# midi_block_template.net
KiCad netlist of a schematic drawn in EAGLE
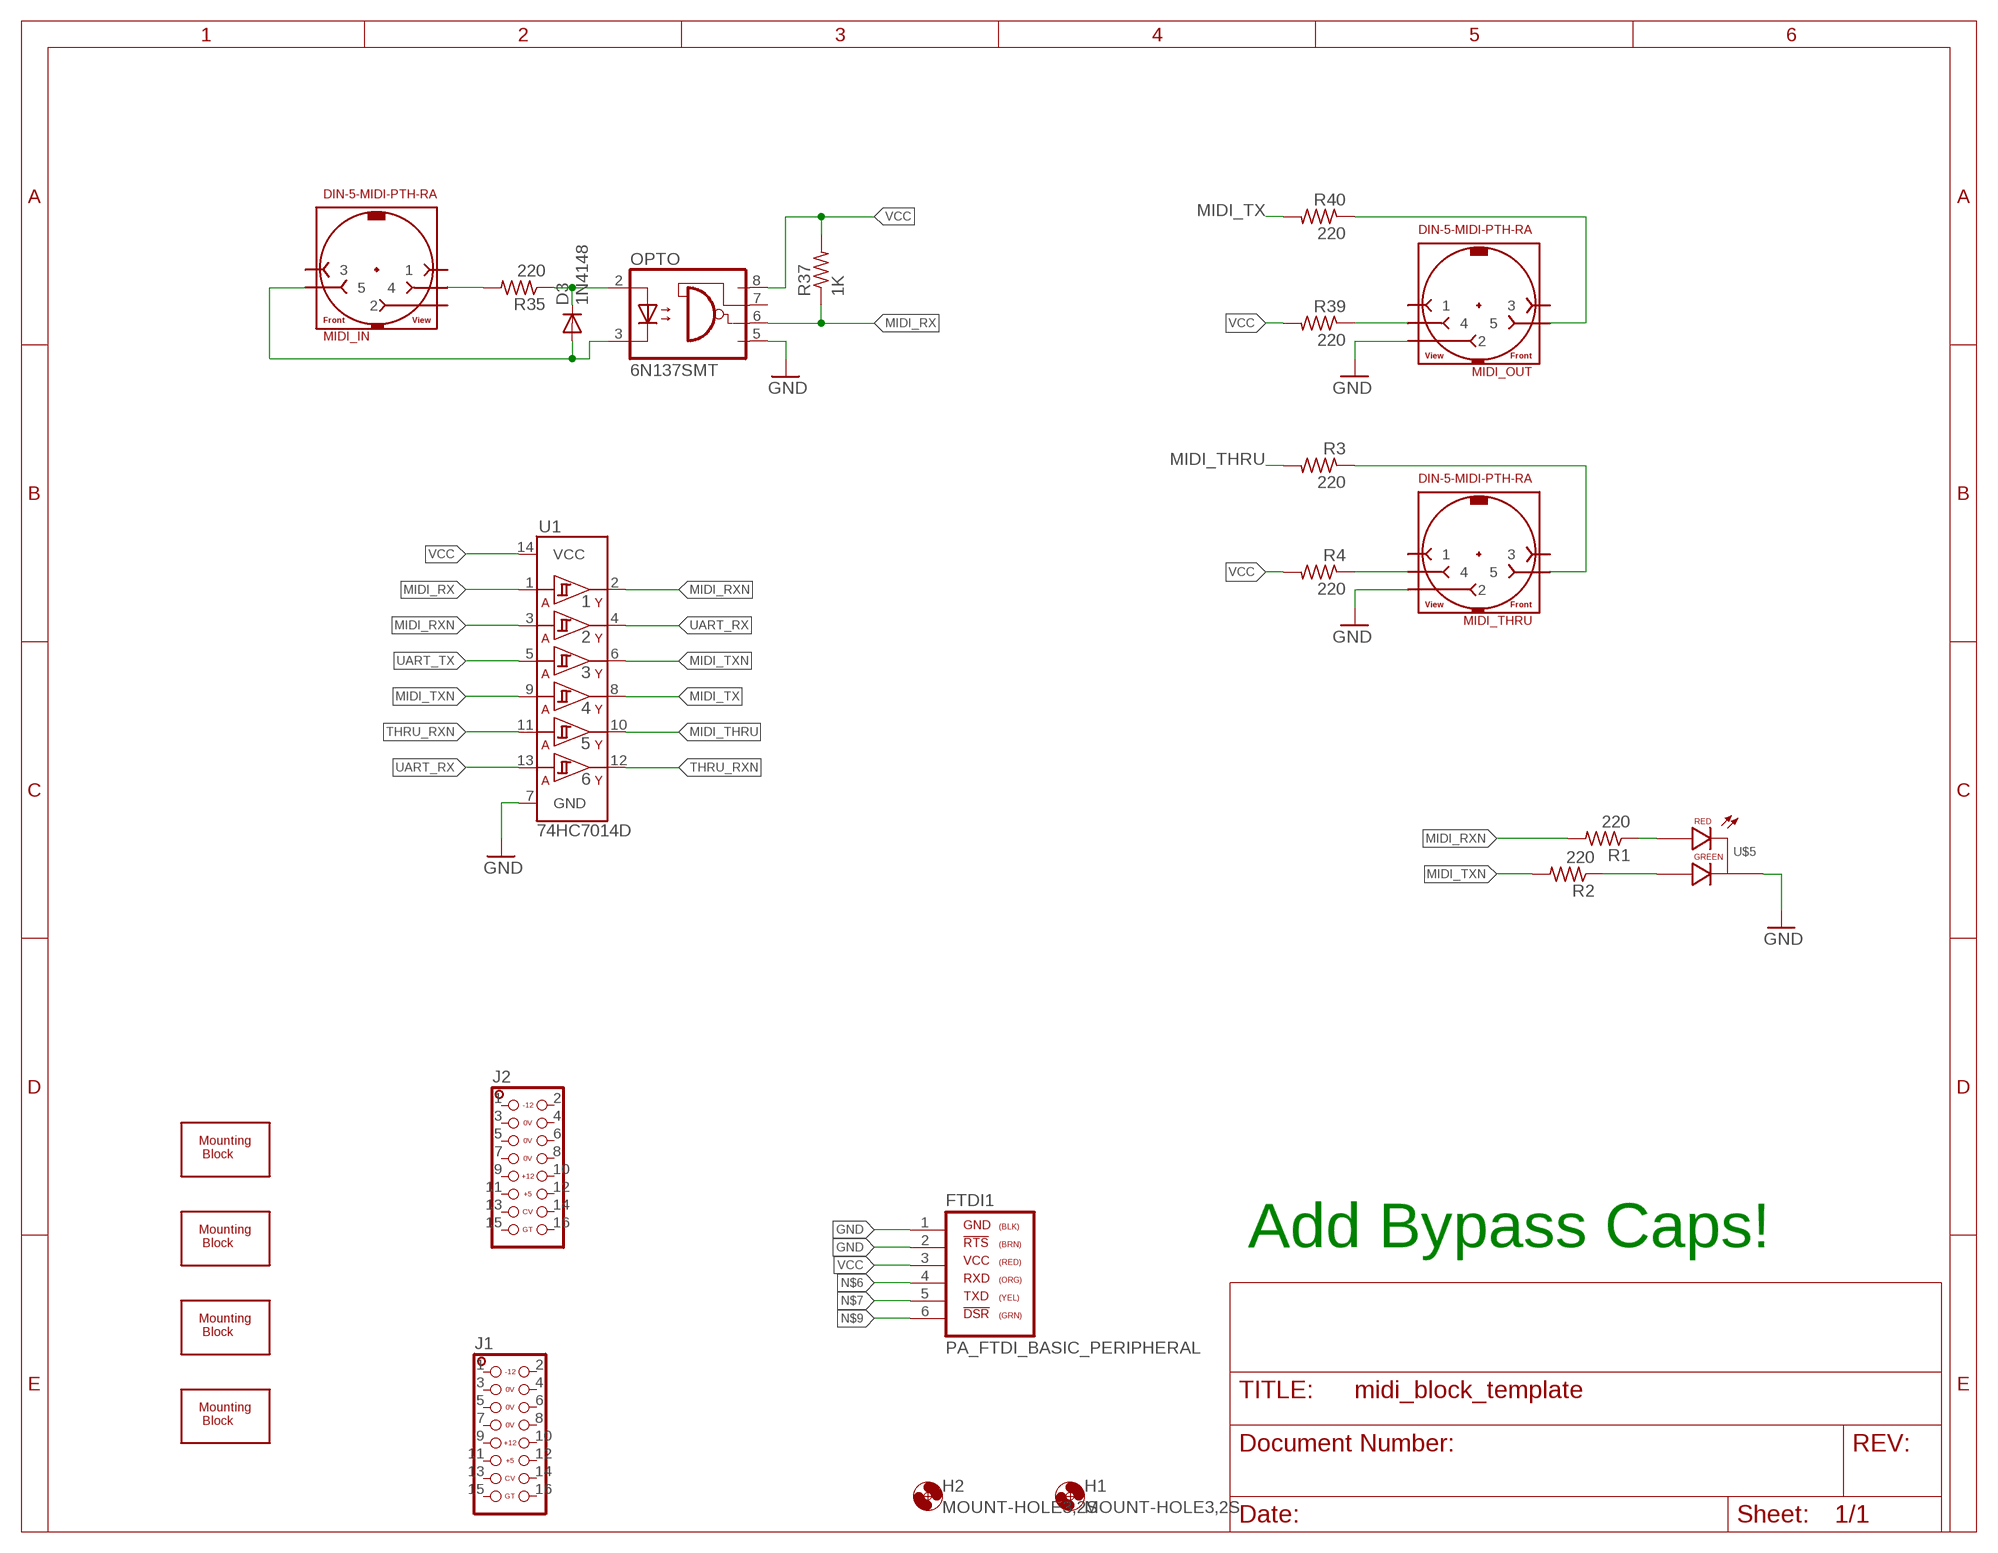
[diagram p0: schematic, sheet 1]

(export (version "E")
  (design (tool "Eeschema 10.0.6"))
  (components
    (comp (ref "D3")
      (value "1N4148")
      (footprint "eagle-import:SOD323-W")
      (libsource (lib "eagle-import") (part "DIODE-SOD323-W"))
    )
    (comp (ref "FTDI1")
      (value "PA_FTDI_BASIC_PERIPHERAL")
      (footprint "eagle-import:PA_PMOD_SIL_MALE")
      (libsource (lib "eagle-import") (part "PA_FTDI_BASIC_PERIPHERAL"))
    )
    (comp (ref "H1")
      (value "MOUNT-HOLE3,2S")
      (footprint "eagle-import:3,2,SMALL")
      (libsource (lib "eagle-import") (part "MOUNT-HOLE3,2S"))
    )
    (comp (ref "H2")
      (value "MOUNT-HOLE3,2S")
      (footprint "eagle-import:3,2,SMALL")
      (libsource (lib "eagle-import") (part "MOUNT-HOLE3,2S"))
    )
    (comp (ref "J1")
      (value "EUROPWR_2X08-SHROUD")
      (footprint "eagle-import:2X08_EUROPWR_SHROUD")
      (libsource (lib "eagle-import") (part "EUROPWR_2X08-SHROUD"))
    )
    (comp (ref "J2")
      (value "EUROPWR_2X08-SHROUD")
      (footprint "eagle-import:2X08_EUROPWR_SHROUD")
      (libsource (lib "eagle-import") (part "EUROPWR_2X08-SHROUD"))
    )
    (comp (ref "MIDI_IN")
      (value "DIN-5-MIDI-PTH-RA")
      (footprint "eagle-import:DIN-5-PTH-RA-SUPPORT")
      (libsource (lib "eagle-import") (part "DIN-5-MIDI-PTH-RA"))
    )
    (comp (ref "MIDI_OUT")
      (value "DIN-5-MIDI-PTH-RA")
      (footprint "eagle-import:DIN-5-PTH-RA-SUPPORT")
      (libsource (lib "eagle-import") (part "DIN-5-MIDI-PTH-RA"))
    )
    (comp (ref "MIDI_THRU")
      (value "DIN-5-MIDI-PTH-RA")
      (footprint "eagle-import:DIN-5-PTH-RA-SUPPORT")
      (libsource (lib "eagle-import") (part "DIN-5-MIDI-PTH-RA"))
    )
    (comp (ref "OPTO")
      (value "6N137SMT")
      (footprint "eagle-import:DIL8-SMD")
      (libsource (lib "eagle-import") (part "6N137SMT"))
    )
    (comp (ref "R1")
      (value "220")
      (footprint "eagle-import:R0603")
      (libsource (lib "eagle-import") (part "R-US_R0603"))
    )
    (comp (ref "R2")
      (value "220")
      (footprint "eagle-import:R0603")
      (libsource (lib "eagle-import") (part "R-US_R0603"))
    )
    (comp (ref "R3")
      (value "220")
      (footprint "eagle-import:R0603")
      (libsource (lib "eagle-import") (part "R-US_R0603"))
    )
    (comp (ref "R4")
      (value "220")
      (footprint "eagle-import:R0603")
      (libsource (lib "eagle-import") (part "R-US_R0603"))
    )
    (comp (ref "R35")
      (value "220")
      (footprint "eagle-import:R0603")
      (libsource (lib "eagle-import") (part "R-US_R0603"))
    )
    (comp (ref "R37")
      (value "1K")
      (footprint "eagle-import:R0603")
      (libsource (lib "eagle-import") (part "R-US_R0603"))
    )
    (comp (ref "R39")
      (value "220")
      (footprint "eagle-import:R0603")
      (libsource (lib "eagle-import") (part "R-US_R0603"))
    )
    (comp (ref "R40")
      (value "220")
      (footprint "eagle-import:R0603")
      (libsource (lib "eagle-import") (part "R-US_R0603"))
    )
    (comp (ref "U$1")
      (value "PCB-MB-SIDE")
      (footprint "eagle-import:PCB-MB-01-SIDE")
      (libsource (lib "eagle-import") (part "PCB-MB-SIDE"))
    )
    (comp (ref "U$2")
      (value "PCB-MB-SIDE")
      (footprint "eagle-import:PCB-MB-01-SIDE")
      (libsource (lib "eagle-import") (part "PCB-MB-SIDE"))
    )
    (comp (ref "U$3")
      (value "PCB-MB-SIDE")
      (footprint "eagle-import:PCB-MB-01-SIDE")
      (libsource (lib "eagle-import") (part "PCB-MB-SIDE"))
    )
    (comp (ref "U$4")
      (value "PCB-MB-SIDE")
      (footprint "eagle-import:PCB-MB-01-SIDE")
      (libsource (lib "eagle-import") (part "PCB-MB-SIDE"))
    )
    (comp (ref "U$5")
      (value "LED-RG-CC-PTH-G18500")
      (footprint "eagle-import:LED-RG-PANEL")
      (libsource (lib "eagle-import") (part "LED-RG-CC-PTH-G18500"))
    )
    (comp (ref "U1")
      (value "74HC7014D")
      (footprint "eagle-import:SOIC-14")
      (libsource (lib "eagle-import") (part "74HC7014D"))
    )
  )
  (nets
    (net (code "1") (name "GND") (class "Default")
      (node (ref "FTDI1") (pin "1") (pinfunction "1_1") (pintype "passive"))
      (node (ref "FTDI1") (pin "2") (pinfunction "2_2") (pintype "passive"))
      (node (ref "MIDI_OUT") (pin "2") (pinfunction "2_2") (pintype "bidirectional"))
      (node (ref "MIDI_THRU") (pin "2") (pinfunction "2_2") (pintype "bidirectional"))
      (node (ref "OPTO") (pin "5") (pinfunction "GND_5") (pintype "passive"))
      (node (ref "U$5") (pin "CC") (pinfunction "CATHODE_CC") (pintype "bidirectional"))
      (node (ref "U1") (pin "7") (pinfunction "GND_7") (pintype "power_in"))
    )
    (net (code "2") (name "MIDI_RX") (class "Default")
      (node (ref "OPTO") (pin "6") (pinfunction "VO_6") (pintype "passive"))
      (node (ref "R37") (pin "1") (pinfunction "1_1") (pintype "passive"))
      (node (ref "U1") (pin "1") (pinfunction "1A_1") (pintype "input"))
    )
    (net (code "3") (name "MIDI_RXN") (class "Default")
      (node (ref "R1") (pin "2") (pinfunction "2_2") (pintype "passive"))
      (node (ref "U1") (pin "2") (pinfunction "1Y_2") (pintype "output"))
      (node (ref "U1") (pin "3") (pinfunction "2A_3") (pintype "input"))
    )
    (net (code "4") (name "MIDI_THRU") (class "Default")
      (node (ref "R3") (pin "2") (pinfunction "2_2") (pintype "passive"))
      (node (ref "U1") (pin "10") (pinfunction "5Y_10") (pintype "output"))
    )
    (net (code "5") (name "MIDI_TX") (class "Default")
      (node (ref "R40") (pin "2") (pinfunction "2_2") (pintype "passive"))
      (node (ref "U1") (pin "8") (pinfunction "4Y_8") (pintype "output"))
    )
    (net (code "6") (name "MIDI_TXN") (class "Default")
      (node (ref "R2") (pin "2") (pinfunction "2_2") (pintype "passive"))
      (node (ref "U1") (pin "6") (pinfunction "3Y_6") (pintype "output"))
      (node (ref "U1") (pin "9") (pinfunction "4A_9") (pintype "input"))
    )
    (net (code "7") (name "N$6") (class "Default")
      (node (ref "FTDI1") (pin "4") (pinfunction "4_4") (pintype "passive"))
    )
    (net (code "8") (name "N$7") (class "Default")
      (node (ref "FTDI1") (pin "5") (pinfunction "5_5") (pintype "passive"))
    )
    (net (code "9") (name "N$9") (class "Default")
      (node (ref "FTDI1") (pin "6") (pinfunction "6_6") (pintype "passive"))
    )
    (net (code "10") (name "Net-(MIDI_IN-Pad4)") (class "Default")
      (node (ref "MIDI_IN") (pin "4") (pinfunction "4_4") (pintype "bidirectional"))
      (node (ref "R35") (pin "2") (pinfunction "2_2") (pintype "passive"))
    )
    (net (code "11") (name "Net-(MIDI_OUT-Pad4)") (class "Default")
      (node (ref "MIDI_OUT") (pin "4") (pinfunction "4_4") (pintype "bidirectional"))
      (node (ref "R39") (pin "1") (pinfunction "1_1") (pintype "passive"))
    )
    (net (code "12") (name "Net-(MIDI_OUT-Pad5)") (class "Default")
      (node (ref "MIDI_OUT") (pin "5") (pinfunction "5_5") (pintype "bidirectional"))
      (node (ref "R40") (pin "1") (pinfunction "1_1") (pintype "passive"))
    )
    (net (code "13") (name "Net-(MIDI_THRU-Pad4)") (class "Default")
      (node (ref "MIDI_THRU") (pin "4") (pinfunction "4_4") (pintype "bidirectional"))
      (node (ref "R4") (pin "1") (pinfunction "1_1") (pintype "passive"))
    )
    (net (code "14") (name "Net-(MIDI_THRU-Pad5)") (class "Default")
      (node (ref "MIDI_THRU") (pin "5") (pinfunction "5_5") (pintype "bidirectional"))
      (node (ref "R3") (pin "1") (pinfunction "1_1") (pintype "passive"))
    )
    (net (code "15") (name "Net-(OPTO-A)") (class "Default")
      (node (ref "D3") (pin "C") (pinfunction "C_C") (pintype "passive"))
      (node (ref "OPTO") (pin "2") (pinfunction "A_2") (pintype "passive"))
      (node (ref "R35") (pin "1") (pinfunction "1_1") (pintype "passive"))
    )
    (net (code "16") (name "Net-(OPTO-C)") (class "Default")
      (node (ref "D3") (pin "A") (pinfunction "A_A") (pintype "passive"))
      (node (ref "MIDI_IN") (pin "5") (pinfunction "5_5") (pintype "bidirectional"))
      (node (ref "OPTO") (pin "3") (pinfunction "C_3") (pintype "passive"))
    )
    (net (code "17") (name "Net-(U$5-GREEN_CATHODE)") (class "Default")
      (node (ref "R2") (pin "1") (pinfunction "1_1") (pintype "passive"))
      (node (ref "U$5") (pin "GREEN") (pinfunction "GREEN_CATHODE_GREEN") (pintype "bidirectional"))
    )
    (net (code "18") (name "Net-(U$5-RED_CATHODE)") (class "Default")
      (node (ref "R1") (pin "1") (pinfunction "1_1") (pintype "passive"))
      (node (ref "U$5") (pin "RED") (pinfunction "RED_CATHODE_RED") (pintype "bidirectional"))
    )
    (net (code "19") (name "THRU_RXN") (class "Default")
      (node (ref "U1") (pin "11") (pinfunction "5A_11") (pintype "input"))
      (node (ref "U1") (pin "12") (pinfunction "6Y_12") (pintype "output"))
    )
    (net (code "20") (name "UART_RX") (class "Default")
      (node (ref "U1") (pin "13") (pinfunction "6A_13") (pintype "input"))
      (node (ref "U1") (pin "4") (pinfunction "2Y_4") (pintype "output"))
    )
    (net (code "21") (name "UART_TX") (class "Default")
      (node (ref "U1") (pin "5") (pinfunction "3A_5") (pintype "input"))
    )
    (net (code "22") (name "VCC") (class "Default")
      (node (ref "FTDI1") (pin "3") (pinfunction "3_3") (pintype "passive"))
      (node (ref "OPTO") (pin "8") (pinfunction "VCC_8") (pintype "passive"))
      (node (ref "R37") (pin "2") (pinfunction "2_2") (pintype "passive"))
      (node (ref "R39") (pin "2") (pinfunction "2_2") (pintype "passive"))
      (node (ref "R4") (pin "2") (pinfunction "2_2") (pintype "passive"))
      (node (ref "U1") (pin "14") (pinfunction "VCC_14") (pintype "power_in"))
    )
    (net (code "23") (name "unconnected-(J1-Pad1)") (class "Default")
      (node (ref "J1") (pin "1") (pinfunction "1_1") (pintype "passive"))
    )
    (net (code "24") (name "unconnected-(J1-Pad2)") (class "Default")
      (node (ref "J1") (pin "2") (pinfunction "2_2") (pintype "passive"))
    )
    (net (code "25") (name "unconnected-(J1-Pad3)") (class "Default")
      (node (ref "J1") (pin "3") (pinfunction "3_3") (pintype "passive"))
    )
    (net (code "26") (name "unconnected-(J1-Pad4)") (class "Default")
      (node (ref "J1") (pin "4") (pinfunction "4_4") (pintype "passive"))
    )
    (net (code "27") (name "unconnected-(J1-Pad5)") (class "Default")
      (node (ref "J1") (pin "5") (pinfunction "5_5") (pintype "passive"))
    )
    (net (code "28") (name "unconnected-(J1-Pad6)") (class "Default")
      (node (ref "J1") (pin "6") (pinfunction "6_6") (pintype "passive"))
    )
    (net (code "29") (name "unconnected-(J1-Pad7)") (class "Default")
      (node (ref "J1") (pin "7") (pinfunction "7_7") (pintype "passive"))
    )
    (net (code "30") (name "unconnected-(J1-Pad8)") (class "Default")
      (node (ref "J1") (pin "8") (pinfunction "8_8") (pintype "passive"))
    )
    (net (code "31") (name "unconnected-(J1-Pad9)") (class "Default")
      (node (ref "J1") (pin "9") (pinfunction "9_9") (pintype "passive"))
    )
    (net (code "32") (name "unconnected-(J1-Pad10)") (class "Default")
      (node (ref "J1") (pin "10") (pinfunction "10_10") (pintype "passive"))
    )
    (net (code "33") (name "unconnected-(J1-Pad11)") (class "Default")
      (node (ref "J1") (pin "11") (pinfunction "11_11") (pintype "passive"))
    )
    (net (code "34") (name "unconnected-(J1-Pad12)") (class "Default")
      (node (ref "J1") (pin "12") (pinfunction "12_12") (pintype "passive"))
    )
    (net (code "35") (name "unconnected-(J1-Pad13)") (class "Default")
      (node (ref "J1") (pin "13") (pinfunction "13_13") (pintype "passive"))
    )
    (net (code "36") (name "unconnected-(J1-Pad14)") (class "Default")
      (node (ref "J1") (pin "14") (pinfunction "14_14") (pintype "passive"))
    )
    (net (code "37") (name "unconnected-(J1-Pad15)") (class "Default")
      (node (ref "J1") (pin "15") (pinfunction "15_15") (pintype "passive"))
    )
    (net (code "38") (name "unconnected-(J1-Pad16)") (class "Default")
      (node (ref "J1") (pin "16") (pinfunction "16_16") (pintype "passive"))
    )
    (net (code "39") (name "unconnected-(J2-Pad1)") (class "Default")
      (node (ref "J2") (pin "1") (pinfunction "1_1") (pintype "passive"))
    )
    (net (code "40") (name "unconnected-(J2-Pad2)") (class "Default")
      (node (ref "J2") (pin "2") (pinfunction "2_2") (pintype "passive"))
    )
    (net (code "41") (name "unconnected-(J2-Pad3)") (class "Default")
      (node (ref "J2") (pin "3") (pinfunction "3_3") (pintype "passive"))
    )
    (net (code "42") (name "unconnected-(J2-Pad4)") (class "Default")
      (node (ref "J2") (pin "4") (pinfunction "4_4") (pintype "passive"))
    )
    (net (code "43") (name "unconnected-(J2-Pad5)") (class "Default")
      (node (ref "J2") (pin "5") (pinfunction "5_5") (pintype "passive"))
    )
    (net (code "44") (name "unconnected-(J2-Pad6)") (class "Default")
      (node (ref "J2") (pin "6") (pinfunction "6_6") (pintype "passive"))
    )
    (net (code "45") (name "unconnected-(J2-Pad7)") (class "Default")
      (node (ref "J2") (pin "7") (pinfunction "7_7") (pintype "passive"))
    )
    (net (code "46") (name "unconnected-(J2-Pad8)") (class "Default")
      (node (ref "J2") (pin "8") (pinfunction "8_8") (pintype "passive"))
    )
    (net (code "47") (name "unconnected-(J2-Pad9)") (class "Default")
      (node (ref "J2") (pin "9") (pinfunction "9_9") (pintype "passive"))
    )
    (net (code "48") (name "unconnected-(J2-Pad10)") (class "Default")
      (node (ref "J2") (pin "10") (pinfunction "10_10") (pintype "passive"))
    )
    (net (code "49") (name "unconnected-(J2-Pad11)") (class "Default")
      (node (ref "J2") (pin "11") (pinfunction "11_11") (pintype "passive"))
    )
    (net (code "50") (name "unconnected-(J2-Pad12)") (class "Default")
      (node (ref "J2") (pin "12") (pinfunction "12_12") (pintype "passive"))
    )
    (net (code "51") (name "unconnected-(J2-Pad13)") (class "Default")
      (node (ref "J2") (pin "13") (pinfunction "13_13") (pintype "passive"))
    )
    (net (code "52") (name "unconnected-(J2-Pad14)") (class "Default")
      (node (ref "J2") (pin "14") (pinfunction "14_14") (pintype "passive"))
    )
    (net (code "53") (name "unconnected-(J2-Pad15)") (class "Default")
      (node (ref "J2") (pin "15") (pinfunction "15_15") (pintype "passive"))
    )
    (net (code "54") (name "unconnected-(J2-Pad16)") (class "Default")
      (node (ref "J2") (pin "16") (pinfunction "16_16") (pintype "passive"))
    )
    (net (code "55") (name "unconnected-(MIDI_IN-Pad1)") (class "Default")
      (node (ref "MIDI_IN") (pin "1") (pinfunction "1_1") (pintype "bidirectional"))
    )
    (net (code "56") (name "unconnected-(MIDI_IN-Pad2)") (class "Default")
      (node (ref "MIDI_IN") (pin "2") (pinfunction "2_2") (pintype "bidirectional"))
    )
    (net (code "57") (name "unconnected-(MIDI_IN-Pad3)") (class "Default")
      (node (ref "MIDI_IN") (pin "3") (pinfunction "3_3") (pintype "bidirectional"))
    )
    (net (code "58") (name "unconnected-(MIDI_OUT-Pad1)") (class "Default")
      (node (ref "MIDI_OUT") (pin "1") (pinfunction "1_1") (pintype "bidirectional"))
    )
    (net (code "59") (name "unconnected-(MIDI_OUT-Pad3)") (class "Default")
      (node (ref "MIDI_OUT") (pin "3") (pinfunction "3_3") (pintype "bidirectional"))
    )
    (net (code "60") (name "unconnected-(MIDI_THRU-Pad1)") (class "Default")
      (node (ref "MIDI_THRU") (pin "1") (pinfunction "1_1") (pintype "bidirectional"))
    )
    (net (code "61") (name "unconnected-(MIDI_THRU-Pad3)") (class "Default")
      (node (ref "MIDI_THRU") (pin "3") (pinfunction "3_3") (pintype "bidirectional"))
    )
    (net (code "62") (name "unconnected-(OPTO-VE-Pad7)") (class "Default")
      (node (ref "OPTO") (pin "7") (pinfunction "VE_7") (pintype "passive"))
    )
  )
)
